# LickSensor.net
KiCad netlist of a schematic drawn in EAGLE
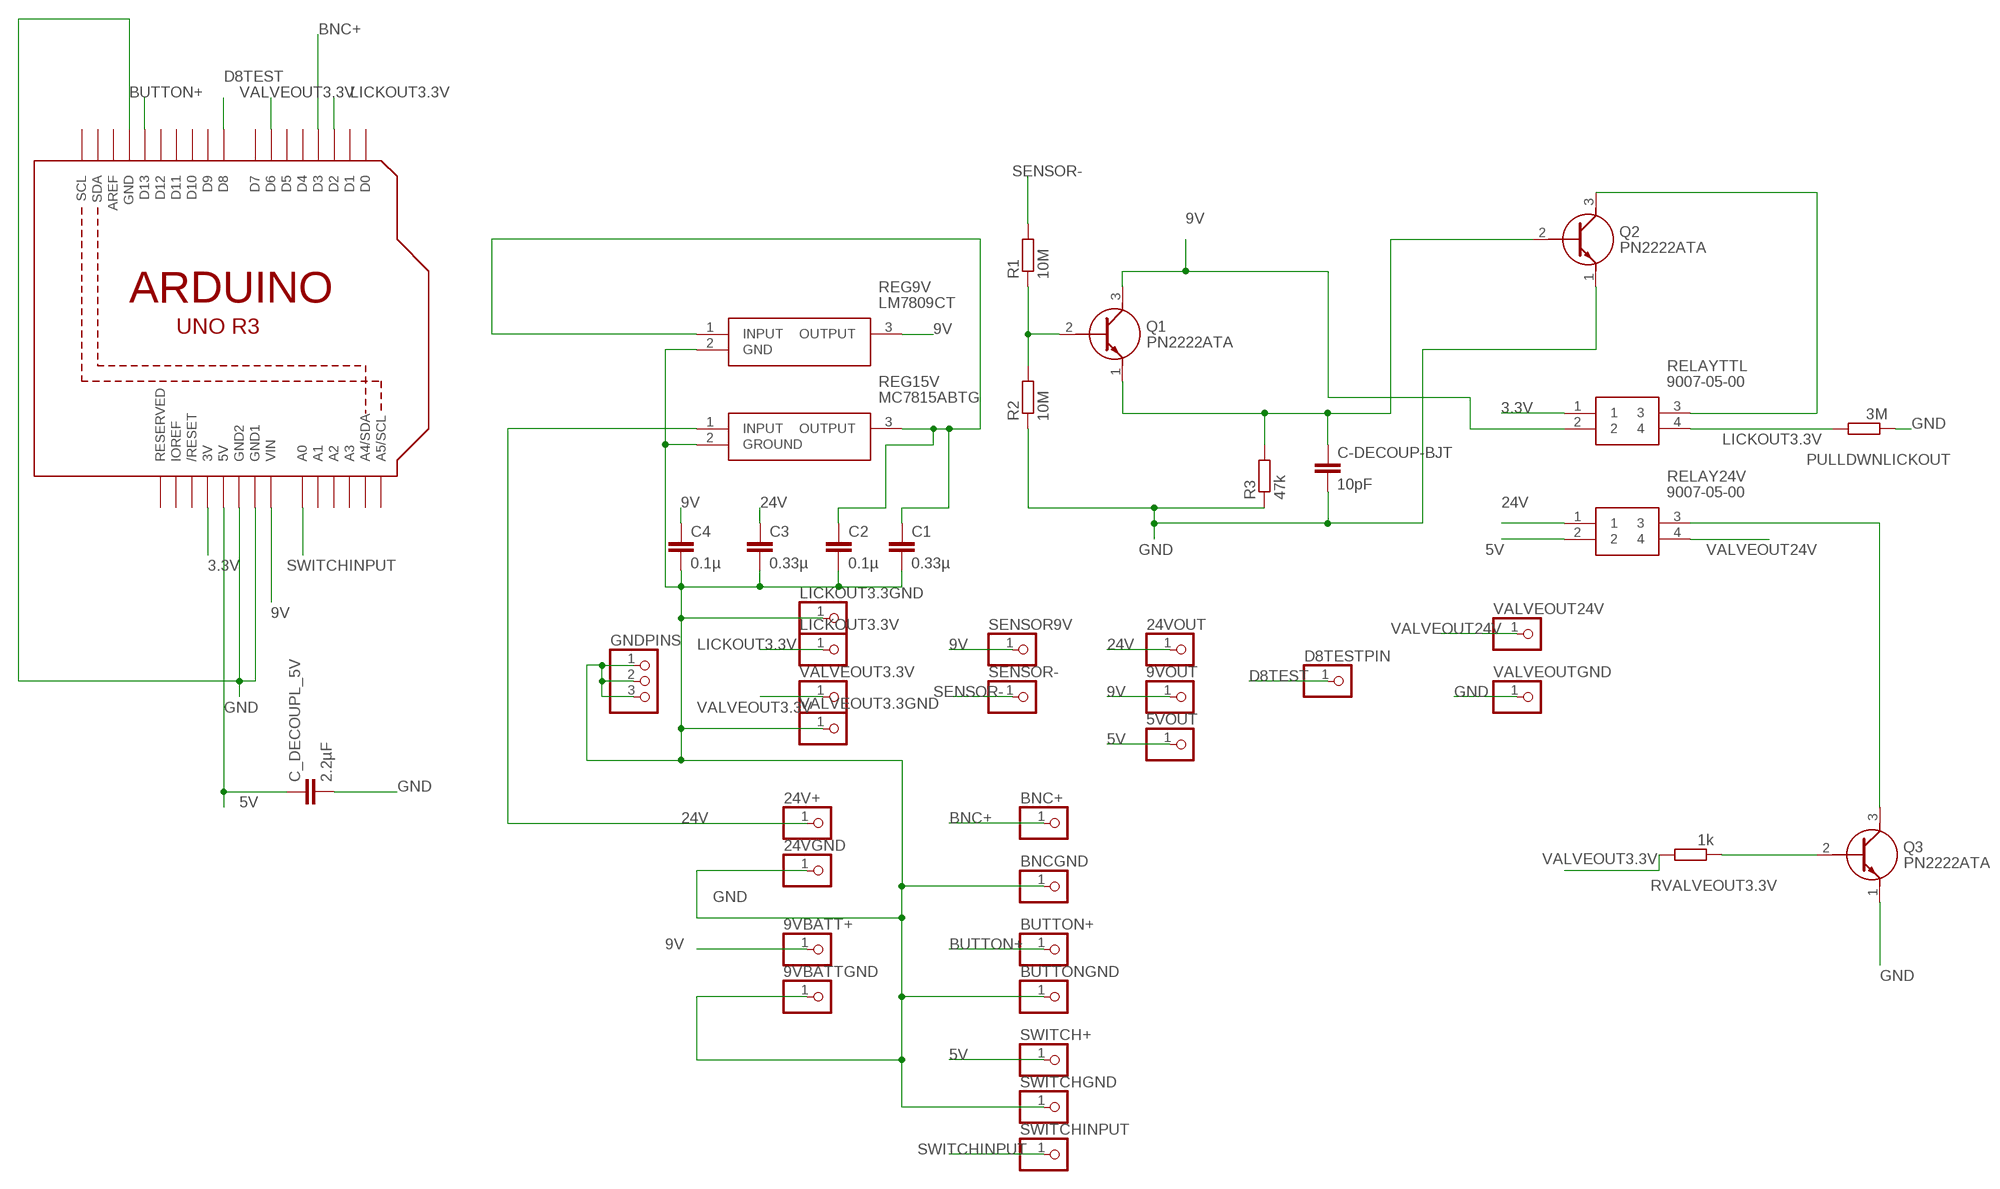
[diagram p0: schematic, sheet 1]

(export (version "E")
  (design (tool "Eeschema 10.0.6"))
  (components
    (comp (ref "5VOUT")
      (value "PINHD-1X1")
      (footprint "eagle-import:1X01")
      (libsource (lib "eagle-import") (part "PINHD-1X1"))
    )
    (comp (ref "9VBATT+")
      (value "PINHD-1X1")
      (footprint "eagle-import:1X01")
      (libsource (lib "eagle-import") (part "PINHD-1X1"))
    )
    (comp (ref "9VBATTGND")
      (value "PINHD-1X1")
      (footprint "eagle-import:1X01")
      (libsource (lib "eagle-import") (part "PINHD-1X1"))
    )
    (comp (ref "9VOUT")
      (value "PINHD-1X1")
      (footprint "eagle-import:1X01")
      (libsource (lib "eagle-import") (part "PINHD-1X1"))
    )
    (comp (ref "24V+")
      (value "PINHD-1X1")
      (footprint "eagle-import:1X01")
      (libsource (lib "eagle-import") (part "PINHD-1X1"))
    )
    (comp (ref "24VGND")
      (value "PINHD-1X1")
      (footprint "eagle-import:1X01")
      (libsource (lib "eagle-import") (part "PINHD-1X1"))
    )
    (comp (ref "24VOUT")
      (value "PINHD-1X1")
      (footprint "eagle-import:1X01")
      (libsource (lib "eagle-import") (part "adafruit_420_PINHD-1X1"))
    )
    (comp (ref "BNC+")
      (value "PINHD-1X1")
      (footprint "eagle-import:1X01")
      (libsource (lib "eagle-import") (part "PINHD-1X1"))
    )
    (comp (ref "BNCGND")
      (value "PINHD-1X1")
      (footprint "eagle-import:1X01")
      (libsource (lib "eagle-import") (part "PINHD-1X1"))
    )
    (comp (ref "BUTTON+")
      (value "PINHD-1X1")
      (footprint "eagle-import:1X01")
      (libsource (lib "eagle-import") (part "PINHD-1X1"))
    )
    (comp (ref "BUTTONGND")
      (value "PINHD-1X1")
      (footprint "eagle-import:1X01")
      (libsource (lib "eagle-import") (part "PINHD-1X1"))
    )
    (comp (ref "C-DECOUP-BJT")
      (value "10pF")
      (footprint "eagle-import:C050-030X075")
      (libsource (lib "eagle-import") (part "C-EU050-030X075"))
    )
    (comp (ref "C1")
      (value "0.33µ")
      (footprint "eagle-import:C5B2.5")
      (libsource (lib "eagle-import") (part "C5/2.5"))
    )
    (comp (ref "C2")
      (value "0.1µ")
      (footprint "eagle-import:C5B2.5")
      (libsource (lib "eagle-import") (part "C5/2.5"))
    )
    (comp (ref "C3")
      (value "0.33µ")
      (footprint "eagle-import:C5B2.5")
      (libsource (lib "eagle-import") (part "C5/2.5"))
    )
    (comp (ref "C4")
      (value "0.1µ")
      (footprint "eagle-import:C5B2.5")
      (libsource (lib "eagle-import") (part "C5/2.5"))
    )
    (comp (ref "C_DECOUPL_5V")
      (value "2.2µF")
      (footprint "eagle-import:C050-030X075")
      (libsource (lib "eagle-import") (part "C-EU050-030X075"))
    )
    (comp (ref "D8TESTPIN")
      (value "PINHD-1X1")
      (footprint "eagle-import:1X01")
      (libsource (lib "eagle-import") (part "adafruit_420_PINHD-1X1"))
    )
    (comp (ref "GNDPINS")
      (value "PINHD-1X3")
      (footprint "eagle-import:1X03")
      (libsource (lib "eagle-import") (part "PINHD-1X3"))
    )
    (comp (ref "LICKOUT3.3GND")
      (value "PINHD-1X1")
      (footprint "eagle-import:1X01")
      (libsource (lib "eagle-import") (part "adafruit_420_PINHD-1X1"))
    )
    (comp (ref "LICKOUT3.3V")
      (value "PINHD-1X1")
      (footprint "eagle-import:1X01")
      (libsource (lib "eagle-import") (part "adafruit_420_PINHD-1X1"))
    )
    (comp (ref "PULLDWNLICKOUT")
      (value "3M")
      (footprint "eagle-import:0207_10")
      (libsource (lib "eagle-import") (part "R-EU_0207/10"))
    )
    (comp (ref "Q1")
      (value "PN2222ATA")
      (footprint "eagle-import:TO-92-3")
      (fields (field (name "MOUSER_PART_NUMBER") "512-PN2222ATA"))
      (libsource (lib "eagle-import") (part "PN2222ATA"))
    )
    (comp (ref "Q2")
      (value "PN2222ATA")
      (footprint "eagle-import:TO-92-3")
      (fields (field (name "MOUSER_PART_NUMBER") "512-PN2222ATA"))
      (libsource (lib "eagle-import") (part "PN2222ATA"))
    )
    (comp (ref "Q3")
      (value "PN2222ATA")
      (footprint "eagle-import:TO-92-3")
      (fields (field (name "MOUSER_PART_NUMBER") "512-PN2222ATA"))
      (libsource (lib "eagle-import") (part "PN2222ATA"))
    )
    (comp (ref "R1")
      (value "10M")
      (footprint "eagle-import:0207_7")
      (libsource (lib "eagle-import") (part "R-EU_0207/7"))
    )
    (comp (ref "R2")
      (value "10M")
      (footprint "eagle-import:0207_7")
      (libsource (lib "eagle-import") (part "R-EU_0207/7"))
    )
    (comp (ref "R3")
      (value "47k")
      (footprint "eagle-import:0207_7")
      (libsource (lib "eagle-import") (part "R-EU_0207/7"))
    )
    (comp (ref "REG9V")
      (value "LM7809CT")
      (footprint "eagle-import:TO254P470X1016X2019-3P")
      (fields (field (name "MOUSER_PART_NUMBER") "512-LM7809CT") (field (name "RS_PART_NUMBER") "7044016"))
      (libsource (lib "eagle-import") (part "LM7809CT"))
    )
    (comp (ref "REG15V")
      (value "MC7815ABTG")
      (footprint "eagle-import:TO254P482X997X2018-3P")
      (fields (field (name "MOUSER_PART_NUMBER") "863-MC7815ABTG") (field (name "RS_PART_NUMBER") "5165944P"))
      (libsource (lib "eagle-import") (part "MC7815ABTG"))
    )
    (comp (ref "RELAY24V")
      (value "9007-05-00")
      (footprint "eagle-import:9007")
      (fields (field (name "MOUSER_PART_NUMBER") "816-9007-05-00"))
      (libsource (lib "eagle-import") (part "9007-05-00"))
    )
    (comp (ref "RELAYTTL")
      (value "9007-05-00")
      (footprint "eagle-import:9007")
      (fields (field (name "MOUSER_PART_NUMBER") "816-9007-05-00"))
      (libsource (lib "eagle-import") (part "9007-05-00"))
    )
    (comp (ref "RVALVEOUT3.3V")
      (value "1k")
      (footprint "eagle-import:0207_10")
      (libsource (lib "eagle-import") (part "R-EU_0207/10"))
    )
    (comp (ref "SENSOR-")
      (value "PINHD-1X1")
      (footprint "eagle-import:1X01")
      (libsource (lib "eagle-import") (part "adafruit_420_PINHD-1X1"))
    )
    (comp (ref "SENSOR9V")
      (value "PINHD-1X1")
      (footprint "eagle-import:1X01")
      (libsource (lib "eagle-import") (part "adafruit_420_PINHD-1X1"))
    )
    (comp (ref "SWITCH+")
      (value "PINHD-1X1")
      (footprint "eagle-import:1X01")
      (libsource (lib "eagle-import") (part "PINHD-1X1"))
    )
    (comp (ref "SWITCHGND")
      (value "PINHD-1X1")
      (footprint "eagle-import:1X01")
      (libsource (lib "eagle-import") (part "PINHD-1X1"))
    )
    (comp (ref "SWITCHINPUT")
      (value "PINHD-1X1")
      (footprint "eagle-import:1X01")
      (libsource (lib "eagle-import") (part "adafruit_420_PINHD-1X1"))
    )
    (comp (ref "U1")
      (value "ARDUINOR3-DIMENSION")
      (footprint "eagle-import:ARDUINOR3")
      (libsource (lib "eagle-import") (part "ARDUINOR3-DIMENSION"))
    )
    (comp (ref "VALVEOUT3.3GND")
      (value "PINHD-1X1")
      (footprint "eagle-import:1X01")
      (libsource (lib "eagle-import") (part "adafruit_420_PINHD-1X1"))
    )
    (comp (ref "VALVEOUT3.3V")
      (value "PINHD-1X1")
      (footprint "eagle-import:1X01")
      (libsource (lib "eagle-import") (part "adafruit_420_PINHD-1X1"))
    )
    (comp (ref "VALVEOUT24V")
      (value "PINHD-1X1")
      (footprint "eagle-import:1X01")
      (libsource (lib "eagle-import") (part "PINHD-1X1"))
    )
    (comp (ref "VALVEOUTGND")
      (value "PINHD-1X1")
      (footprint "eagle-import:1X01")
      (libsource (lib "eagle-import") (part "PINHD-1X1"))
    )
  )
  (nets
    (net (code "1") (name "/3.3V") (class "Default")
      (node (ref "RELAYTTL") (pin "1") (pinfunction "1_1") (pintype "bidirectional"))
      (node (ref "U1") (pin "3V") (pinfunction "3V_3V") (pintype "power_in"))
    )
    (net (code "2") (name "/5V") (class "Default")
      (node (ref "5VOUT") (pin "1") (pinfunction "1_1") (pintype "passive"))
      (node (ref "C_DECOUPL_5V") (pin "1") (pinfunction "1_1") (pintype "passive"))
      (node (ref "RELAY24V") (pin "2") (pinfunction "2_2") (pintype "bidirectional"))
      (node (ref "SWITCH+") (pin "1") (pinfunction "1_1") (pintype "passive"))
      (node (ref "U1") (pin "5V") (pinfunction "5V_5V") (pintype "power_in"))
    )
    (net (code "3") (name "/9V") (class "Default")
      (node (ref "9VBATT+") (pin "1") (pinfunction "1_1") (pintype "passive"))
      (node (ref "9VOUT") (pin "1") (pinfunction "1_1") (pintype "passive"))
      (node (ref "C4") (pin "1") (pinfunction "1_1") (pintype "passive"))
      (node (ref "Q1") (pin "3") (pinfunction "C_3") (pintype "bidirectional"))
      (node (ref "REG9V") (pin "3") (pinfunction "OUTPUT_3") (pintype "bidirectional"))
      (node (ref "RELAYTTL") (pin "2") (pinfunction "2_2") (pintype "bidirectional"))
      (node (ref "SENSOR9V") (pin "1") (pinfunction "1_1") (pintype "passive"))
      (node (ref "U1") (pin "VIN") (pinfunction "VIN_VIN") (pintype "power_in"))
    )
    (net (code "4") (name "/24V") (class "Default")
      (node (ref "24V+") (pin "1") (pinfunction "1_1") (pintype "passive"))
      (node (ref "24VOUT") (pin "1") (pinfunction "1_1") (pintype "passive"))
      (node (ref "C3") (pin "1") (pinfunction "1_1") (pintype "passive"))
      (node (ref "REG15V") (pin "1") (pinfunction "INPUT_1") (pintype "input"))
      (node (ref "RELAY24V") (pin "1") (pinfunction "1_1") (pintype "bidirectional"))
    )
    (net (code "5") (name "/BNC+") (class "Default")
      (node (ref "BNC+") (pin "1") (pinfunction "1_1") (pintype "passive"))
      (node (ref "U1") (pin "D3") (pinfunction "D3_D3") (pintype "bidirectional"))
    )
    (net (code "6") (name "/BUTTON+") (class "Default")
      (node (ref "BUTTON+") (pin "1") (pinfunction "1_1") (pintype "passive"))
      (node (ref "U1") (pin "D13") (pinfunction "D13_D13") (pintype "bidirectional"))
    )
    (net (code "7") (name "/D8TEST") (class "Default")
      (node (ref "D8TESTPIN") (pin "1") (pinfunction "1_1") (pintype "passive"))
      (node (ref "U1") (pin "D8") (pinfunction "D8_D8") (pintype "bidirectional"))
    )
    (net (code "8") (name "/GND") (class "Default")
      (node (ref "24VGND") (pin "1") (pinfunction "1_1") (pintype "passive"))
      (node (ref "9VBATTGND") (pin "1") (pinfunction "1_1") (pintype "passive"))
      (node (ref "BNCGND") (pin "1") (pinfunction "1_1") (pintype "passive"))
      (node (ref "BUTTONGND") (pin "1") (pinfunction "1_1") (pintype "passive"))
      (node (ref "C-DECOUP-BJT") (pin "2") (pinfunction "2_2") (pintype "passive"))
      (node (ref "C1") (pin "2") (pinfunction "2_2") (pintype "passive"))
      (node (ref "C2") (pin "2") (pinfunction "2_2") (pintype "passive"))
      (node (ref "C3") (pin "2") (pinfunction "2_2") (pintype "passive"))
      (node (ref "C4") (pin "2") (pinfunction "2_2") (pintype "passive"))
      (node (ref "C_DECOUPL_5V") (pin "2") (pinfunction "2_2") (pintype "passive"))
      (node (ref "GNDPINS") (pin "1") (pinfunction "1_1") (pintype "passive"))
      (node (ref "GNDPINS") (pin "2") (pinfunction "2_2") (pintype "passive"))
      (node (ref "GNDPINS") (pin "3") (pinfunction "3_3") (pintype "passive"))
      (node (ref "LICKOUT3.3GND") (pin "1") (pinfunction "1_1") (pintype "passive"))
      (node (ref "PULLDWNLICKOUT") (pin "1") (pinfunction "1_1") (pintype "passive"))
      (node (ref "Q2") (pin "1") (pinfunction "E_1") (pintype "bidirectional"))
      (node (ref "Q3") (pin "1") (pinfunction "E_1") (pintype "bidirectional"))
      (node (ref "R2") (pin "1") (pinfunction "1_1") (pintype "passive"))
      (node (ref "R3") (pin "1") (pinfunction "1_1") (pintype "passive"))
      (node (ref "REG15V") (pin "2") (pinfunction "GROUND_2") (pintype "power_in"))
      (node (ref "REG9V") (pin "2") (pinfunction "GND_2") (pintype "bidirectional"))
      (node (ref "SWITCHGND") (pin "1") (pinfunction "1_1") (pintype "passive"))
      (node (ref "U1") (pin "GND") (pinfunction "GND_GND") (pintype "power_in"))
      (node (ref "U1") (pin "GND1") (pinfunction "GND1_GND1") (pintype "power_in"))
      (node (ref "U1") (pin "GND2") (pinfunction "GND2_GND2") (pintype "power_in"))
      (node (ref "VALVEOUT3.3GND") (pin "1") (pinfunction "1_1") (pintype "passive"))
      (node (ref "VALVEOUTGND") (pin "1") (pinfunction "1_1") (pintype "passive"))
    )
    (net (code "9") (name "/LICKOUT3.3V") (class "Default")
      (node (ref "LICKOUT3.3V") (pin "1") (pinfunction "1_1") (pintype "passive"))
      (node (ref "PULLDWNLICKOUT") (pin "2") (pinfunction "2_2") (pintype "passive"))
      (node (ref "RELAYTTL") (pin "4") (pinfunction "4_4") (pintype "bidirectional"))
      (node (ref "U1") (pin "D2") (pinfunction "D2_D2") (pintype "bidirectional"))
    )
    (net (code "10") (name "/SENSOR-") (class "Default")
      (node (ref "R1") (pin "2") (pinfunction "2_2") (pintype "passive"))
      (node (ref "SENSOR-") (pin "1") (pinfunction "1_1") (pintype "passive"))
    )
    (net (code "11") (name "/SWITCHINPUT") (class "Default")
      (node (ref "SWITCHINPUT") (pin "1") (pinfunction "1_1") (pintype "passive"))
      (node (ref "U1") (pin "A0") (pinfunction "A0_A0") (pintype "bidirectional"))
    )
    (net (code "12") (name "/VALVEOUT3.3V") (class "Default")
      (node (ref "RVALVEOUT3.3V") (pin "2") (pinfunction "2_2") (pintype "passive"))
      (node (ref "U1") (pin "D6") (pinfunction "D6_D6") (pintype "bidirectional"))
      (node (ref "VALVEOUT3.3V") (pin "1") (pinfunction "1_1") (pintype "passive"))
    )
    (net (code "13") (name "/VALVEOUT24V") (class "Default")
      (node (ref "RELAY24V") (pin "4") (pinfunction "4_4") (pintype "bidirectional"))
      (node (ref "VALVEOUT24V") (pin "1") (pinfunction "1_1") (pintype "passive"))
    )
    (net (code "14") (name "Net-(Q1-B)") (class "Default")
      (node (ref "Q1") (pin "2") (pinfunction "B_2") (pintype "bidirectional"))
      (node (ref "R1") (pin "1") (pinfunction "1_1") (pintype "passive"))
      (node (ref "R2") (pin "2") (pinfunction "2_2") (pintype "passive"))
    )
    (net (code "15") (name "Net-(Q1-E)") (class "Default")
      (node (ref "C-DECOUP-BJT") (pin "1") (pinfunction "1_1") (pintype "passive"))
      (node (ref "Q1") (pin "1") (pinfunction "E_1") (pintype "bidirectional"))
      (node (ref "Q2") (pin "2") (pinfunction "B_2") (pintype "bidirectional"))
      (node (ref "R3") (pin "2") (pinfunction "2_2") (pintype "passive"))
    )
    (net (code "16") (name "Net-(Q2-C)") (class "Default")
      (node (ref "Q2") (pin "3") (pinfunction "C_3") (pintype "bidirectional"))
      (node (ref "RELAYTTL") (pin "3") (pinfunction "3_3") (pintype "bidirectional"))
    )
    (net (code "17") (name "Net-(Q3-B)") (class "Default")
      (node (ref "Q3") (pin "2") (pinfunction "B_2") (pintype "bidirectional"))
      (node (ref "RVALVEOUT3.3V") (pin "1") (pinfunction "1_1") (pintype "passive"))
    )
    (net (code "18") (name "Net-(Q3-C)") (class "Default")
      (node (ref "Q3") (pin "3") (pinfunction "C_3") (pintype "bidirectional"))
      (node (ref "RELAY24V") (pin "3") (pinfunction "3_3") (pintype "bidirectional"))
    )
    (net (code "19") (name "Net-(REG15V-OUTPUT)") (class "Default")
      (node (ref "C1") (pin "1") (pinfunction "1_1") (pintype "passive"))
      (node (ref "C2") (pin "1") (pinfunction "1_1") (pintype "passive"))
      (node (ref "REG15V") (pin "3") (pinfunction "OUTPUT_3") (pintype "output"))
      (node (ref "REG9V") (pin "1") (pinfunction "INPUT_1") (pintype "bidirectional"))
    )
    (net (code "20") (name "unconnected-(U1-A4{slash}SDA-PadA4)") (class "Default")
      (node (ref "U1") (pin "A4") (pinfunction "A4/SDA_A4") (pintype "bidirectional"))
    )
    (net (code "21") (name "unconnected-(U1-A5{slash}SCL-PadA5)") (class "Default")
      (node (ref "U1") (pin "A5") (pinfunction "A5/SCL_A5") (pintype "bidirectional"))
    )
    (net (code "22") (name "unconnected-(U1-PadA1)") (class "Default")
      (node (ref "U1") (pin "A1") (pinfunction "A1_A1") (pintype "bidirectional"))
    )
    (net (code "23") (name "unconnected-(U1-PadA2)") (class "Default")
      (node (ref "U1") (pin "A2") (pinfunction "A2_A2") (pintype "bidirectional"))
    )
    (net (code "24") (name "unconnected-(U1-PadA3)") (class "Default")
      (node (ref "U1") (pin "A3") (pinfunction "A3_A3") (pintype "bidirectional"))
    )
    (net (code "25") (name "unconnected-(U1-PadAREF)") (class "Default")
      (node (ref "U1") (pin "AREF") (pinfunction "AREF_AREF") (pintype "bidirectional"))
    )
    (net (code "26") (name "unconnected-(U1-PadD0)") (class "Default")
      (node (ref "U1") (pin "D0") (pinfunction "D0_D0") (pintype "bidirectional"))
    )
    (net (code "27") (name "unconnected-(U1-PadD1)") (class "Default")
      (node (ref "U1") (pin "D1") (pinfunction "D1_D1") (pintype "bidirectional"))
    )
    (net (code "28") (name "unconnected-(U1-PadD4)") (class "Default")
      (node (ref "U1") (pin "D4") (pinfunction "D4_D4") (pintype "bidirectional"))
    )
    (net (code "29") (name "unconnected-(U1-PadD5)") (class "Default")
      (node (ref "U1") (pin "D5") (pinfunction "D5_D5") (pintype "bidirectional"))
    )
    (net (code "30") (name "unconnected-(U1-PadD7)") (class "Default")
      (node (ref "U1") (pin "D7") (pinfunction "D7_D7") (pintype "bidirectional"))
    )
    (net (code "31") (name "unconnected-(U1-PadD9)") (class "Default")
      (node (ref "U1") (pin "D9") (pinfunction "D9_D9") (pintype "bidirectional"))
    )
    (net (code "32") (name "unconnected-(U1-PadD10)") (class "Default")
      (node (ref "U1") (pin "D10") (pinfunction "D10_D10") (pintype "bidirectional"))
    )
    (net (code "33") (name "unconnected-(U1-PadD11)") (class "Default")
      (node (ref "U1") (pin "D11") (pinfunction "D11_D11") (pintype "bidirectional"))
    )
    (net (code "34") (name "unconnected-(U1-PadD12)") (class "Default")
      (node (ref "U1") (pin "D12") (pinfunction "D12_D12") (pintype "bidirectional"))
    )
    (net (code "35") (name "unconnected-(U1-PadIOREF)") (class "Default")
      (node (ref "U1") (pin "IOREF") (pinfunction "IOREF_IOREF") (pintype "output"))
    )
    (net (code "36") (name "unconnected-(U1-PadRESERVED)") (class "Default")
      (node (ref "U1") (pin "RESERVED") (pinfunction "RESERVED_RESERVED") (pintype "no_connect"))
    )
    (net (code "37") (name "unconnected-(U1-PadSCL)") (class "Default")
      (node (ref "U1") (pin "SCL") (pinfunction "SCL_SCL") (pintype "bidirectional"))
    )
    (net (code "38") (name "unconnected-(U1-PadSDA)") (class "Default")
      (node (ref "U1") (pin "SDA") (pinfunction "SDA_SDA") (pintype "bidirectional"))
    )
    (net (code "39") (name "unconnected-(U1-{slash}RESET-PadRESET)") (class "Default")
      (node (ref "U1") (pin "RESET") (pinfunction "/RESET_RESET") (pintype "bidirectional"))
    )
  )
)
